# 92_KEY.net
KiCad netlist of a schematic drawn in Altium Designer
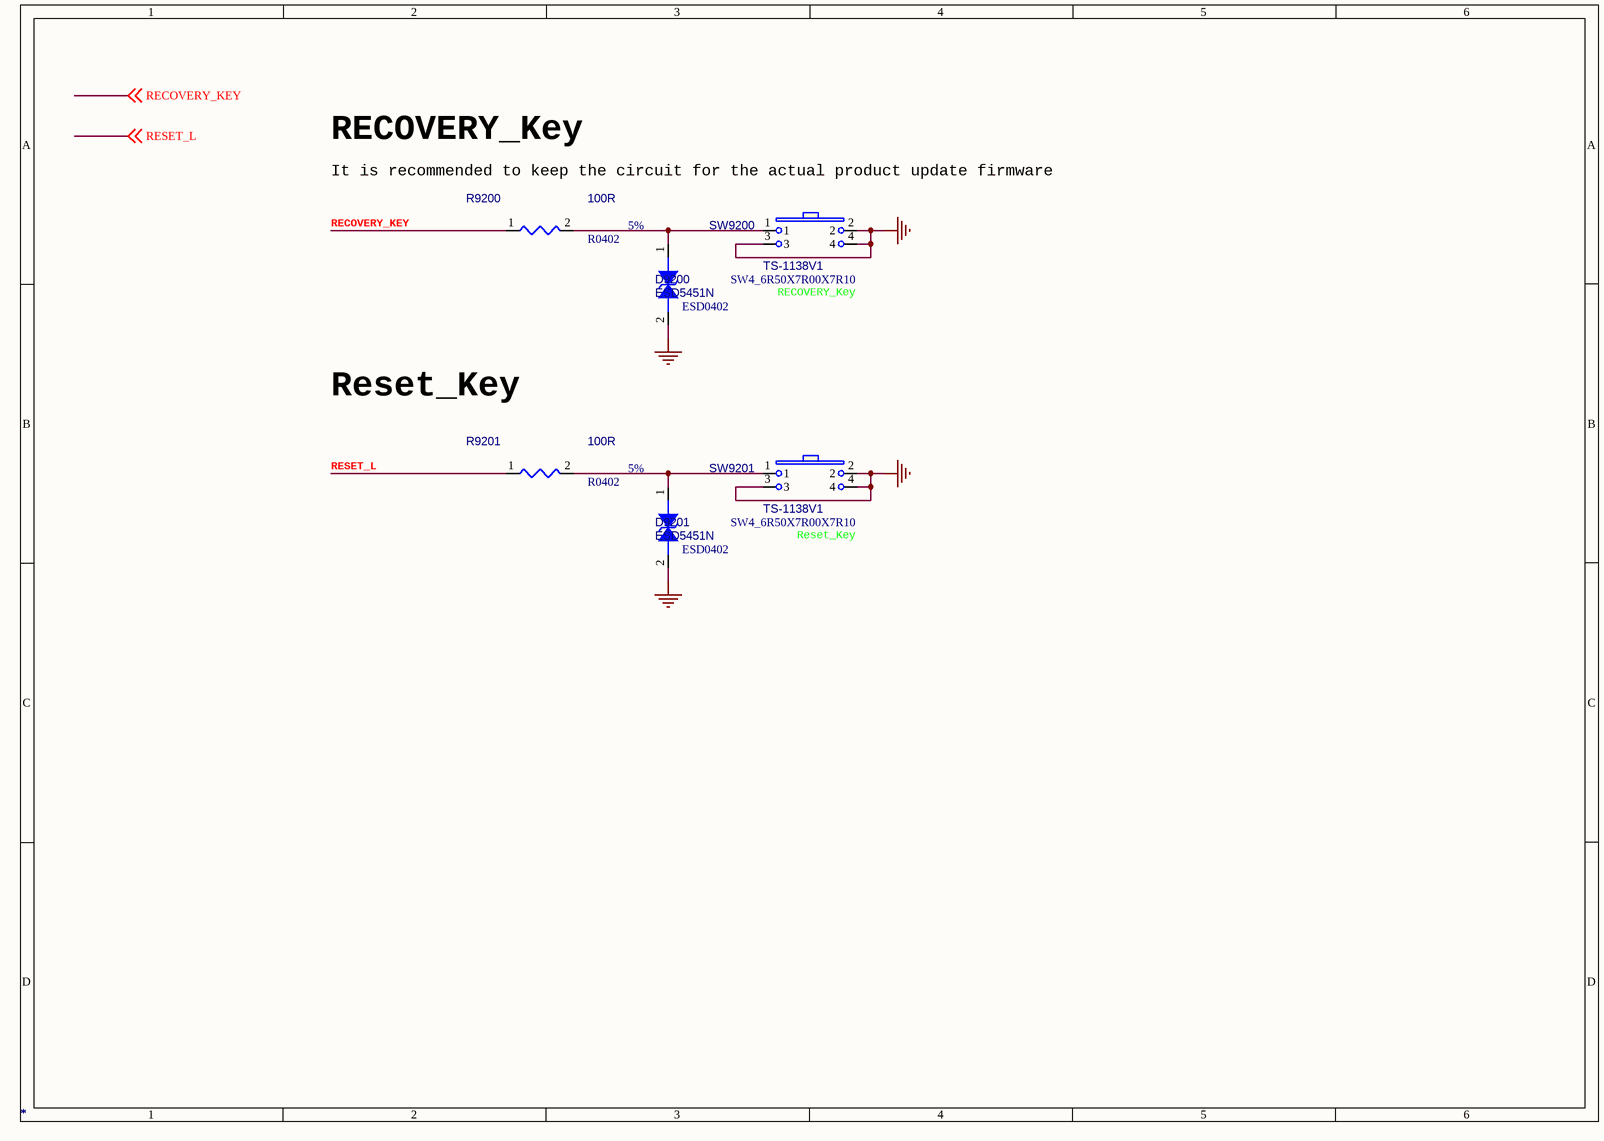
[diagram p0: 92.KEY.SchDoc]

(export (version "E")
  (design (tool "Eeschema 10.0.6"))
  (components
    (comp (ref "D9200")
      (value "*")
      (footprint "ESD0402")
      (description "1-Line, Bi-directional, Transient Voltage Suppressors.17.5pF.")
      (fields
        (field (name "PCB FOOTPRINT") "ESD0402")
        (field (name "MANUFACTURER") "WillSemi(О¤¶ы°лµјМе)")
        (field (name "ALTIUM_UNNAMED_1") "ESD5451N")
        (field (name "CREATED BY") "JJJ")
      )
      (libsource (lib "*") (part "DIODE BI_DIR TRIG"))
    )
    (comp (ref "D9201")
      (value "*")
      (footprint "ESD0402")
      (description "1-Line, Bi-directional, Transient Voltage Suppressors.17.5pF.")
      (fields
        (field (name "PCB FOOTPRINT") "ESD0402")
        (field (name "MANUFACTURER") "WillSemi(О¤¶ы°лµјМе)")
        (field (name "ALTIUM_UNNAMED_1") "ESD5451N")
        (field (name "CREATED BY") "JJJ")
      )
      (libsource (lib "*") (part "DIODE BI_DIR TRIG"))
    )
    (comp (ref "R9200")
      (value "*")
      (footprint "R0402")
      (description "НЁУГєсД¤µзЧи,100R,+/-5%,R0402,1/16W.")
      (fields
        (field (name "PCB FOOTPRINT") "R0402")
        (field (name "TOLERANCE") "5%")
        (field (name "MANUFACTURER") "YAGEO")
        (field (name "ALTIUM_UNNAMED_1") "100R")
        (field (name "CREATED BY") "YTL")
      )
      (libsource (lib "*") (part "RESISTOR_Dup1"))
    )
    (comp (ref "R9201")
      (value "*")
      (footprint "R0402")
      (description "НЁУГєсД¤µзЧи,100R,+/-5%,R0402,1/16W.")
      (fields
        (field (name "PCB FOOTPRINT") "R0402")
        (field (name "TOLERANCE") "5%")
        (field (name "MANUFACTURER") "YAGEO")
        (field (name "ALTIUM_UNNAMED_1") "100R")
        (field (name "CREATED BY") "YTL")
      )
      (libsource (lib "*") (part "RESISTOR_Dup1"))
    )
    (comp (ref "SW9200")
      (value "*")
      (footprint "YC-6615B")
      (description "4ЅЕЈ¬Іа±ЯЈ¬ІејюЈ¬6.5MMx7.1MM°ґјь")
      (fields
        (field (name "PCB FOOTPRINT") "SW4_6R50X7R00X7R10")
        (field (name "OPTION") "RECOVERY_Key")
        (field (name "MANUFACTURER PART NUMBER") "TS-1138V1")
        (field (name "MANUFACTURER") "Сw»ЄµзЧУ")
        (field (name "ALTIUM_UNNAMED_1") "TS-1138V1")
        (field (name "CREATED BY") "YWQ")
      )
      (libsource (lib "*") (part "KEY_4PIN"))
    )
    (comp (ref "SW9201")
      (value "*")
      (footprint "YC-6615B")
      (description "4ЅЕЈ¬Іа±ЯЈ¬ІејюЈ¬6.5MMx7.1MM°ґјь")
      (fields
        (field (name "PCB FOOTPRINT") "SW4_6R50X7R00X7R10")
        (field (name "MANUFACTURER") "Сw»ЄµзЧУ")
        (field (name "MANUFACTURER PART NUMBER") "TS-1138V1")
        (field (name "OPTION") "Reset_Key")
        (field (name "ALTIUM_UNNAMED_1") "TS-1138V1")
        (field (name "CREATED BY") "YWQ")
      )
      (libsource (lib "*") (part "KEY_4PIN"))
    )
  )
  (nets
    (net (code "1") (name "GND") (class "Default")
      (node (ref "D9200") (pin "2") (pinfunction "2_2") (pintype "passive"))
      (node (ref "D9201") (pin "2") (pinfunction "2_2") (pintype "passive"))
      (node (ref "SW9200") (pin "2") (pinfunction "2_2") (pintype "passive"))
      (node (ref "SW9200") (pin "3") (pinfunction "3_3") (pintype "passive"))
      (node (ref "SW9200") (pin "4") (pinfunction "4_4") (pintype "passive"))
      (node (ref "SW9201") (pin "2") (pinfunction "2_2") (pintype "passive"))
      (node (ref "SW9201") (pin "3") (pinfunction "3_3") (pintype "passive"))
      (node (ref "SW9201") (pin "4") (pinfunction "4_4") (pintype "passive"))
    )
    (net (code "2") (name "Net-(D9200-Pad1)") (class "Default")
      (node (ref "D9200") (pin "1") (pinfunction "1_1") (pintype "passive"))
      (node (ref "R9200") (pin "2") (pinfunction "2_2") (pintype "passive"))
      (node (ref "SW9200") (pin "1") (pinfunction "1_1") (pintype "passive"))
    )
    (net (code "3") (name "Net-(D9201-Pad1)") (class "Default")
      (node (ref "D9201") (pin "1") (pinfunction "1_1") (pintype "passive"))
      (node (ref "R9201") (pin "2") (pinfunction "2_2") (pintype "passive"))
      (node (ref "SW9201") (pin "1") (pinfunction "1_1") (pintype "passive"))
    )
    (net (code "4") (name "RECOVERY_KEY") (class "Default")
      (node (ref "R9200") (pin "1") (pinfunction "1_1") (pintype "passive"))
    )
    (net (code "5") (name "RESET_L") (class "Default")
      (node (ref "R9201") (pin "1") (pinfunction "1_1") (pintype "passive"))
    )
  )
)
